# MLX90614.net
KiCad netlist of a schematic drawn in EAGLE
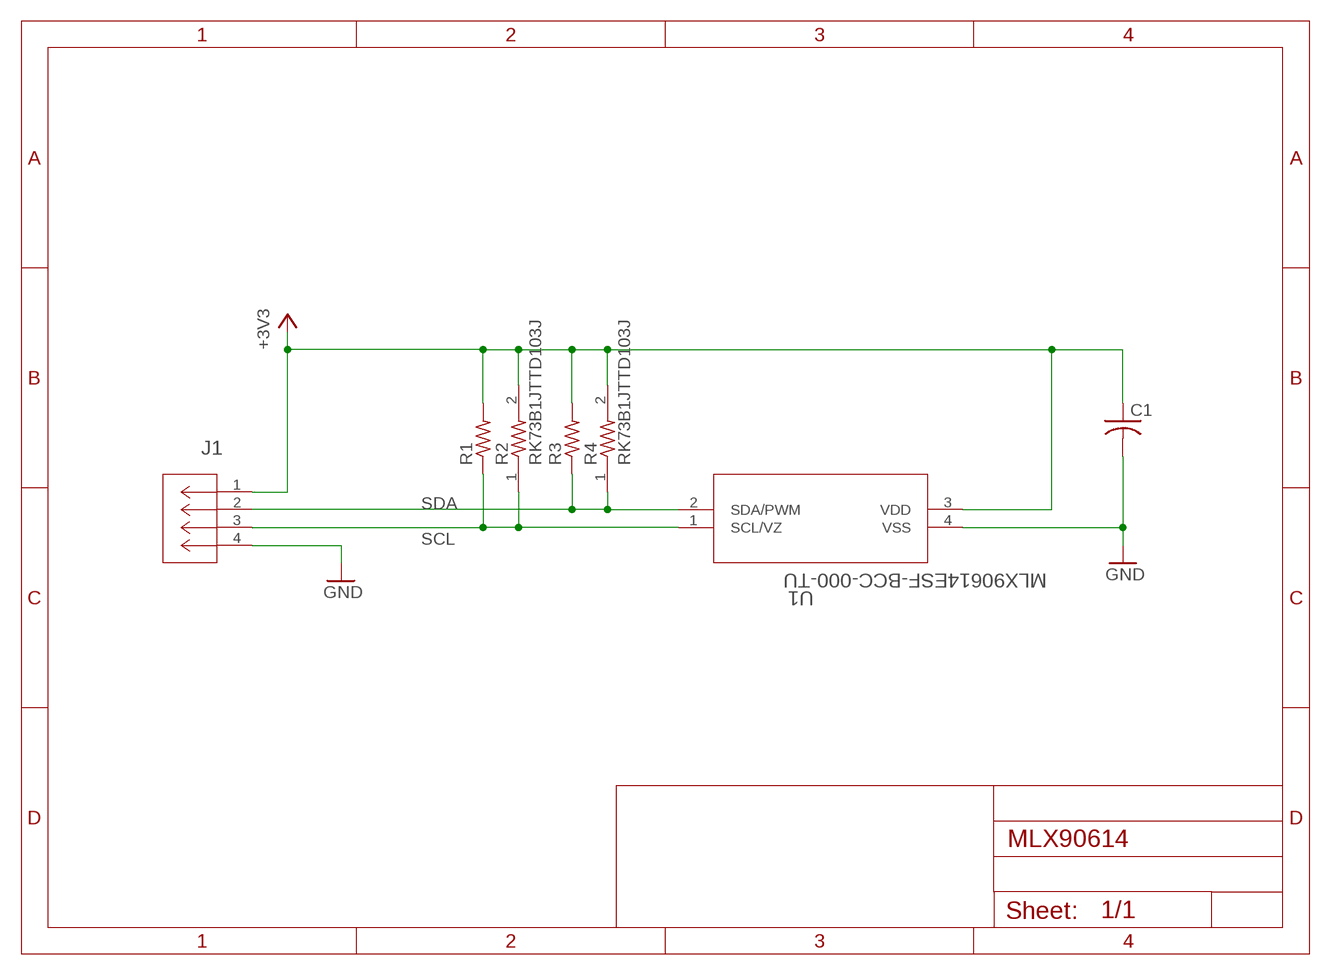
[diagram p0: schematic, sheet 1]

(export (version "E")
  (design (tool "Eeschema 10.0.6"))
  (components
    (comp (ref "C1")
      (value "C-US025-024X044")
      (footprint "eagle-import:C025-024X044")
      (libsource (lib "eagle-import") (part "C-US025-024X044"))
    )
    (comp (ref "J1")
      (value "S4B-PH-K-S(LF)(SN)")
      (footprint "eagle-import:CONN_S4B-PH-K-S_JST")
      (fields (field (name "COPYRIGHT") "Copyright (C) 2023 Ultra Librarian. All rights reserved."))
      (libsource (lib "eagle-import") (part "S4B-PH-K-S(LF)(SN)"))
    )
    (comp (ref "R1")
      (value "R-US_0204/7")
      (footprint "eagle-import:0204_7")
      (libsource (lib "eagle-import") (part "R-US_0204/7"))
    )
    (comp (ref "R2")
      (value "RK73B1JTTD103J")
      (footprint "eagle-import:RESC1608X55N")
      (fields
        (field (name "DIGI-KEY_PART_NUMBER") "2019-RK73B1JTTD103JCT-ND")
        (field (name "MF") "KOA Speer")
      )
      (libsource (lib "eagle-import") (part "RK73B1JTTD103J"))
    )
    (comp (ref "R3")
      (value "R-US_0204/7")
      (footprint "eagle-import:0204_7")
      (libsource (lib "eagle-import") (part "R-US_0204/7"))
    )
    (comp (ref "R4")
      (value "RK73B1JTTD103J")
      (footprint "eagle-import:RESC1608X55N")
      (fields
        (field (name "DIGI-KEY_PART_NUMBER") "2019-RK73B1JTTD103JCT-ND")
        (field (name "MF") "KOA Speer")
      )
      (libsource (lib "eagle-import") (part "RK73B1JTTD103J"))
    )
    (comp (ref "U1")
      (value "MLX90614ESF-BCC-000-TU")
      (footprint "eagle-import:MLX90614XCC_MEL")
      (fields (field (name "COPYRIGHT") "Copyright (C) 2023 Ultra Librarian. All rights reserved."))
      (libsource (lib "eagle-import") (part "MLX90614ESF-BCC-000-TU"))
    )
  )
  (nets
    (net (code "1") (name "+3V3") (class "Default")
      (node (ref "C1") (pin "1") (pinfunction "1_1") (pintype "passive"))
      (node (ref "J1") (pin "1") (pinfunction "1_1") (pintype "passive"))
      (node (ref "R1") (pin "2") (pinfunction "2_2") (pintype "passive"))
      (node (ref "R2") (pin "2") (pinfunction "2_2") (pintype "passive"))
      (node (ref "R3") (pin "2") (pinfunction "2_2") (pintype "passive"))
      (node (ref "R4") (pin "2") (pinfunction "2_2") (pintype "passive"))
      (node (ref "U1") (pin "3") (pinfunction "VDD_3") (pintype "power_in"))
    )
    (net (code "2") (name "/SCL") (class "Default")
      (node (ref "J1") (pin "3") (pinfunction "3_3") (pintype "passive"))
      (node (ref "R1") (pin "1") (pinfunction "1_1") (pintype "passive"))
      (node (ref "R2") (pin "1") (pinfunction "1_1") (pintype "passive"))
      (node (ref "U1") (pin "1") (pinfunction "SCL/VZ_1") (pintype "input"))
    )
    (net (code "3") (name "/SDA") (class "Default")
      (node (ref "J1") (pin "2") (pinfunction "2_2") (pintype "passive"))
      (node (ref "R3") (pin "1") (pinfunction "1_1") (pintype "passive"))
      (node (ref "R4") (pin "1") (pinfunction "1_1") (pintype "passive"))
      (node (ref "U1") (pin "2") (pinfunction "SDA/PWM_2") (pintype "bidirectional"))
    )
    (net (code "4") (name "GND") (class "Default")
      (node (ref "C1") (pin "2") (pinfunction "2_2") (pintype "passive"))
      (node (ref "J1") (pin "4") (pinfunction "4_4") (pintype "passive"))
      (node (ref "U1") (pin "4") (pinfunction "VSS_4") (pintype "passive"))
    )
  )
)
